# Battery_Load_Share_V2.net
KiCad netlist of a schematic drawn in Altium Designer
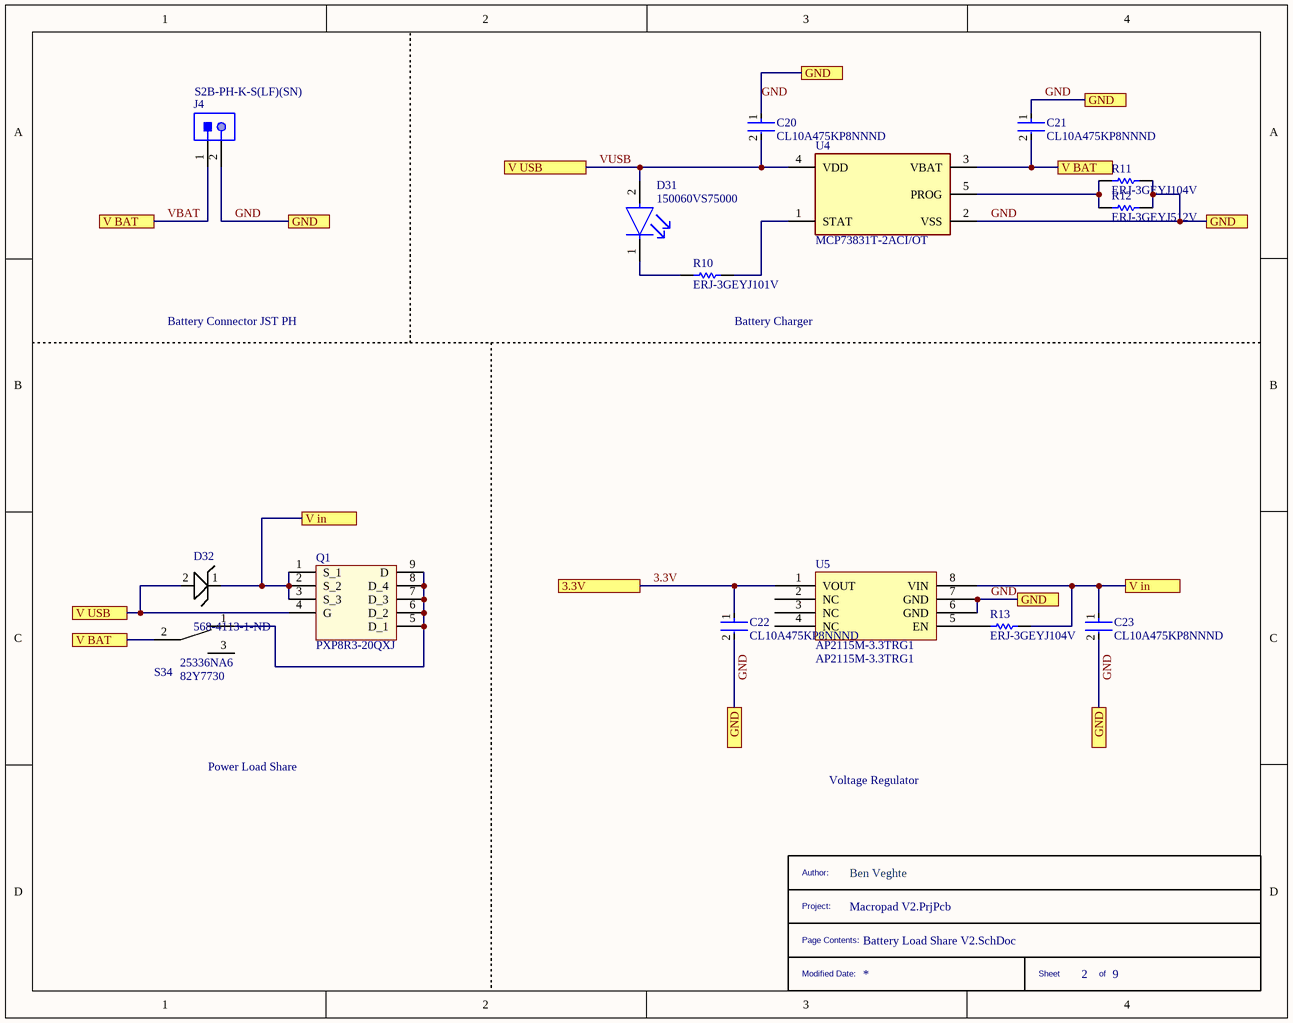
[diagram p0: Battery Load Share V2.SchDoc]

(export (version "E")
  (design (tool "Eeschema 10.0.6"))
  (components
    (comp (ref "C20")
      (value "CL10A475KP8NNND")
      (footprint "FP-CL10-IPC_C")
      (description "Cap Ceramic 4.7uF 10V X5R ±10% Pad SMD 0603 +85°C T/R")
      (fields (field (name "TOLERANCE") "10%"))
      (libsource (lib "Altium Content Vault") (part "b4654b650e69147ec39a6b967a45e02"))
    )
    (comp (ref "C21")
      (value "CL10A475KP8NNND")
      (footprint "FP-CL10-IPC_C")
      (description "Cap Ceramic 4.7uF 10V X5R ±10% Pad SMD 0603 +85°C T/R")
      (fields (field (name "TOLERANCE") "10%"))
      (libsource (lib "Altium Content Vault") (part "b4654b650e69147ec39a6b967a45e02"))
    )
    (comp (ref "C22")
      (value "CL10A475KP8NNND")
      (footprint "FP-CL10-IPC_C")
      (description "Cap Ceramic 4.7uF 10V X5R ±10% Pad SMD 0603 +85°C T/R")
      (fields (field (name "TOLERANCE") "10%"))
      (libsource (lib "Altium Content Vault") (part "b4654b650e69147ec39a6b967a45e02"))
    )
    (comp (ref "C23")
      (value "CL10A475KP8NNND")
      (footprint "FP-CL10-IPC_C")
      (description "Cap Ceramic 4.7uF 10V X5R ±10% Pad SMD 0603 +85°C T/R")
      (fields (field (name "TOLERANCE") "10%"))
      (libsource (lib "Altium Content Vault") (part "b4654b650e69147ec39a6b967a45e02"))
    )
    (comp (ref "D31")
      (value "150060VS75000")
      (footprint "FP-150060VS75000-MFG")
      (description "LED GREEN CLEAR 0603 SMD")
      (libsource (lib "Altium Content Vault") (part "8706943c75ba83719d021d2fdc84c58"))
    )
    (comp (ref "D32")
      (value "PMEG2010AEJ115")
      (footprint "PMEG2010AEJ")
      (fields
        (field (name "MANUFACTURER") "NXP Semiconductors")
        (field (name "SUPPLIER PART NUMBER 1") "568-4113-1-ND")
      )
      (libsource (lib "Universal Parts") (part "PMEG2010AEJ115"))
    )
    (comp (ref "J4")
      (value "S2B-PH-K-S(LF)(SN)")
      (footprint "JST-S2B-PH-K-S_V")
      (fields (field (name "TOLERANCE") "20%"))
      (libsource (lib "Altium Content Vault") (part "CN-1P-M-R2"))
    )
    (comp (ref "Q1")
      (value "PXP8R3-20QXJ")
      (footprint "PXP8R3-20QXJ")
      (description "PXP8R3-20QX - 20 V, P-channel Trench MOSFET")
      (fields (field (name "MANUFACTURER") "Nexperia") (field (name "SUPPLIER PART NUMBER 1") "PXP8R3-20QXJ"))
      (libsource (lib "Universal Parts") (part "PXP8R3-20QXJ"))
    )
    (comp (ref "R10")
      (value "ERJ-3GEYJ101V")
      (footprint "RESC1608X55X30LL15T15")
      (fields (field (name "MANUFACTURER") "Panasonic"))
      (libsource (lib "Altium Content Vault") (part "RES"))
    )
    (comp (ref "R11")
      (value "ERJ-3GEYJ104V")
      (footprint "RESC1608X55X30NL15T15")
      (fields (field (name "MANUFACTURER") "Panasonic"))
      (libsource (lib "Altium Content Vault") (part "RES"))
    )
    (comp (ref "R12")
      (value "ERJ-3GEYJ512V")
      (footprint "RESC1608X55X30LL15T15")
      (fields (field (name "MANUFACTURER") "Panasonic"))
      (libsource (lib "Altium Content Vault") (part "RES"))
    )
    (comp (ref "R13")
      (value "ERJ-3GEYJ104V")
      (footprint "RESC1608X55X30NL15T15")
      (fields (field (name "MANUFACTURER") "Panasonic"))
      (libsource (lib "Altium Content Vault") (part "RES"))
    )
    (comp (ref "S34")
      (value "25336NA6")
      (footprint "25336NA6")
      (description "Switch Slide ON ON SPDT Side Slide 1A 30VDC 20000Cycles PC Pins Thru-Hole")
      (fields (field (name "MANUFACTURER") "APEM") (field (name "SUPPLIER PART NUMBER 1") "82Y7730"))
      (libsource (lib "Universal Parts") (part "25336NA6"))
    )
    (comp (ref "U4")
      (value "MCP73831T-2ACI/OT")
      (footprint "FP-C04-091-OT-IPC_B")
      (description "IC CONTROLLR LI-ION 4.2V SOT23-5")
      (libsource (lib "Altium Content Vault") (part "61f5a3bb3429d9e0caadea342aa3b19"))
    )
    (comp (ref "U5")
      (value "AP2115M-3.3TRG1")
      (footprint "AP2115M-3.3TRG1")
      (description "LDO Regulator Pos 3.3V 1A 8-Pin SOIC T/R")
      (fields
        (field (name "MANUFACTURER") "Diodes")
        (field (name "SUPPLIER PART NUMBER 1") "AP2115M-3.3TRG1")
      )
      (libsource (lib "Universal Parts") (part "AP2115M-3.3TRG1"))
    )
  )
  (nets
    (net (code "1") (name "/3.3V") (class "Default")
      (node (ref "C22") (pin "1") (pinfunction "1_1") (pintype "passive"))
      (node (ref "U5") (pin "1") (pinfunction "VOUT_1") (pintype "passive"))
    )
    (net (code "2") (name "/GND") (class "Default")
      (node (ref "C20") (pin "1") (pinfunction "1_1") (pintype "passive"))
      (node (ref "C21") (pin "1") (pinfunction "1_1") (pintype "passive"))
      (node (ref "C22") (pin "2") (pinfunction "2_2") (pintype "passive"))
      (node (ref "C23") (pin "2") (pinfunction "2_2") (pintype "passive"))
      (node (ref "J4") (pin "2") (pinfunction "2_2") (pintype "passive"))
      (node (ref "R11") (pin "2") (pinfunction "2_2") (pintype "passive"))
      (node (ref "R12") (pin "2") (pinfunction "2_2") (pintype "passive"))
      (node (ref "U4") (pin "2") (pinfunction "VSS_2") (pintype "power_in"))
      (node (ref "U5") (pin "6") (pinfunction "GND_6") (pintype "passive"))
      (node (ref "U5") (pin "7") (pinfunction "GND_7") (pintype "passive"))
    )
    (net (code "3") (name "/V in") (class "Default")
      (node (ref "C23") (pin "1") (pinfunction "1_1") (pintype "passive"))
      (node (ref "D32") (pin "1") (pinfunction "34_1") (pintype "passive"))
      (node (ref "Q1") (pin "1") (pinfunction "S_1_1") (pintype "passive"))
      (node (ref "Q1") (pin "2") (pinfunction "S_2_2") (pintype "passive"))
      (node (ref "Q1") (pin "3") (pinfunction "S_3_3") (pintype "passive"))
      (node (ref "R13") (pin "2") (pinfunction "2_2") (pintype "passive"))
      (node (ref "U5") (pin "8") (pinfunction "VIN_8") (pintype "passive"))
    )
    (net (code "4") (name "/VBAT") (class "Default")
      (node (ref "C21") (pin "2") (pinfunction "2_2") (pintype "passive"))
      (node (ref "J4") (pin "1") (pinfunction "1_1") (pintype "passive"))
      (node (ref "S34") (pin "2") (pinfunction "1_2") (pintype "passive"))
      (node (ref "U4") (pin "3") (pinfunction "VBAT_3") (pintype "power_in"))
    )
    (net (code "5") (name "/VUSB") (class "Default")
      (node (ref "C20") (pin "2") (pinfunction "2_2") (pintype "passive"))
      (node (ref "D31") (pin "2") (pinfunction "A_2") (pintype "passive"))
      (node (ref "D32") (pin "2") (pinfunction "35_2") (pintype "passive"))
      (node (ref "Q1") (pin "4") (pinfunction "G_4") (pintype "passive"))
      (node (ref "U4") (pin "4") (pinfunction "VDD_4") (pintype "power_in"))
    )
    (net (code "6") (name "Net-(D31-C)") (class "Default")
      (node (ref "D31") (pin "1") (pinfunction "C_1") (pintype "passive"))
      (node (ref "R10") (pin "1") (pinfunction "1_1") (pintype "passive"))
    )
    (net (code "7") (name "Net-(Q1-D)") (class "Default")
      (node (ref "Q1") (pin "5") (pinfunction "D_1_5") (pintype "passive"))
      (node (ref "Q1") (pin "6") (pinfunction "D_2_6") (pintype "passive"))
      (node (ref "Q1") (pin "7") (pinfunction "D_3_7") (pintype "passive"))
      (node (ref "Q1") (pin "8") (pinfunction "D_4_8") (pintype "passive"))
      (node (ref "Q1") (pin "9") (pinfunction "D_9") (pintype "passive"))
      (node (ref "S34") (pin "1") (pinfunction "1_1") (pintype "passive"))
    )
    (net (code "8") (name "Net-(U4-PROG)") (class "Default")
      (node (ref "R11") (pin "1") (pinfunction "1_1") (pintype "passive"))
      (node (ref "R12") (pin "1") (pinfunction "1_1") (pintype "passive"))
      (node (ref "U4") (pin "5") (pinfunction "PROG_5") (pintype "passive"))
    )
    (net (code "9") (name "Net-(U4-STAT)") (class "Default")
      (node (ref "R10") (pin "2") (pinfunction "2_2") (pintype "passive"))
      (node (ref "U4") (pin "1") (pinfunction "STAT_1") (pintype "passive"))
    )
    (net (code "10") (name "Net-(U5-EN)") (class "Default")
      (node (ref "R13") (pin "1") (pinfunction "1_1") (pintype "passive"))
      (node (ref "U5") (pin "5") (pinfunction "EN_5") (pintype "passive"))
    )
    (net (code "11") (name "unconnected-(S34-Pad3)") (class "Default")
      (node (ref "S34") (pin "3") (pinfunction "3_3") (pintype "passive"))
    )
    (net (code "12") (name "unconnected-(U5-NC-Pad2)") (class "Default")
      (node (ref "U5") (pin "2") (pinfunction "NC_2") (pintype "passive"))
    )
    (net (code "13") (name "unconnected-(U5-NC-Pad3)") (class "Default")
      (node (ref "U5") (pin "3") (pinfunction "NC_3") (pintype "passive"))
    )
    (net (code "14") (name "unconnected-(U5-NC-Pad4)") (class "Default")
      (node (ref "U5") (pin "4") (pinfunction "NC_4") (pintype "passive"))
    )
  )
)
